# Supplies.net
KiCad netlist of a schematic drawn in Altium Designer
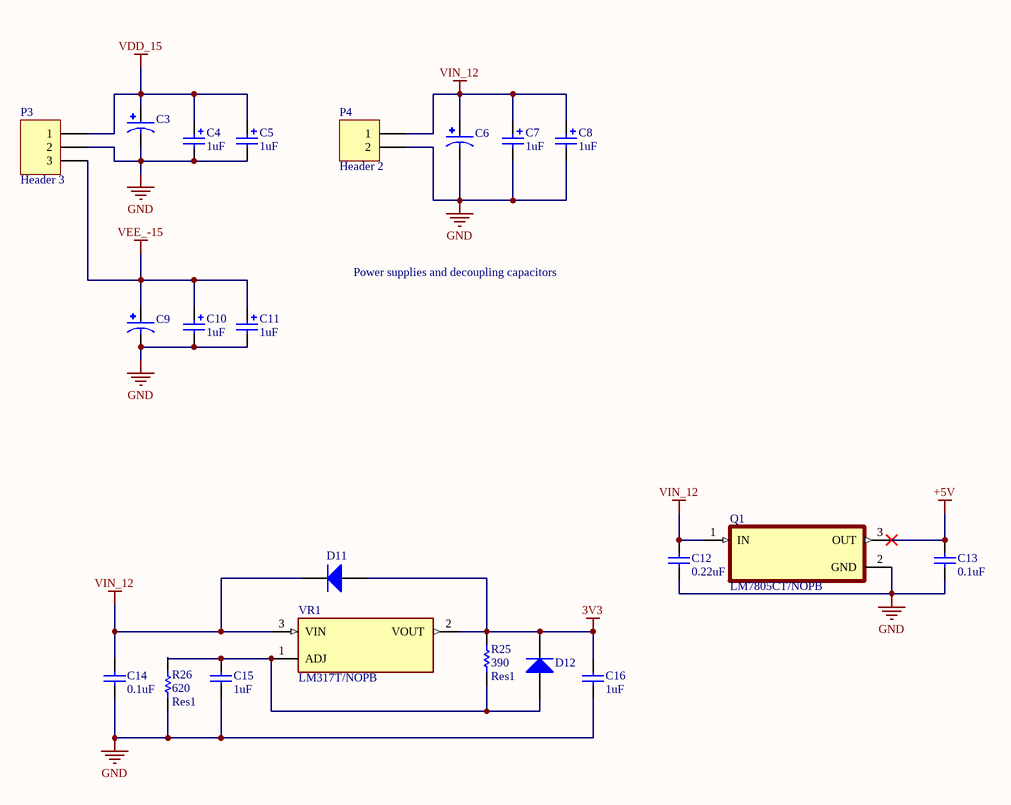
[diagram p0: Supplies.SchDoc]

(export (version "E")
  (design (tool "Eeschema 10.0.6"))
  (components
    (comp (ref "C3")
      (value "ECA2AM100B")
      (footprint "CAPPRD500W50D500H1100")
      (description "10ÂµF 100V Aluminum Electrolytic Capacitors Radial, Can 2000 Hrs @ 85Â°C")
      (fields (field (name "MF") "Panasonic") (field (name "DIGI-KEY_PART_NUMBER") "P19556TB-ND"))
      (libsource (lib "10uF_capa_rad2ECA2AM100B") (part "ECA2AM100B"))
    )
    (comp (ref "C4")
      (value "1uF")
      (footprint "RAD-0.1")
      (description "Polarized Capacitor (Radial)")
      (fields (field (name "Comment") "Cap No Pol") (field (name "PUBLISHER") "Altium Limited"))
      (libsource (lib "LABSTEPS_Project") (part "Cap No Pol"))
    )
    (comp (ref "C5")
      (value "1uF")
      (footprint "RAD-0.1")
      (description "Polarized Capacitor (Radial)")
      (fields (field (name "Comment") "Cap No Pol") (field (name "PUBLISHER") "Altium Limited"))
      (libsource (lib "LABSTEPS_Project") (part "Cap No Pol"))
    )
    (comp (ref "C6")
      (value "ECA2AM100B")
      (footprint "CAPPRD500W50D500H1100")
      (description "10ÂµF 100V Aluminum Electrolytic Capacitors Radial, Can 2000 Hrs @ 85Â°C")
      (fields (field (name "MF") "Panasonic") (field (name "DIGI-KEY_PART_NUMBER") "P19556TB-ND"))
      (libsource (lib "10uF_capa_rad2ECA2AM100B") (part "ECA2AM100B"))
    )
    (comp (ref "C7")
      (value "1uF")
      (footprint "RAD-0.1")
      (description "Polarized Capacitor (Radial)")
      (fields (field (name "Comment") "Cap No Pol") (field (name "PUBLISHER") "Altium Limited"))
      (libsource (lib "LABSTEPS_Project") (part "Cap No Pol"))
    )
    (comp (ref "C8")
      (value "1uF")
      (footprint "RAD-0.1")
      (description "Polarized Capacitor (Radial)")
      (fields (field (name "Comment") "Cap No Pol") (field (name "PUBLISHER") "Altium Limited"))
      (libsource (lib "LABSTEPS_Project") (part "Cap No Pol"))
    )
    (comp (ref "C9")
      (value "ECA2AM100B")
      (footprint "CAPPRD500W50D500H1100")
      (description "10ÂµF 100V Aluminum Electrolytic Capacitors Radial, Can 2000 Hrs @ 85Â°C")
      (fields (field (name "MF") "Panasonic") (field (name "DIGI-KEY_PART_NUMBER") "P19556TB-ND"))
      (libsource (lib "10uF_capa_rad2ECA2AM100B") (part "ECA2AM100B"))
    )
    (comp (ref "C10")
      (value "1uF")
      (footprint "RAD-0.1")
      (description "Polarized Capacitor (Radial)")
      (fields (field (name "Comment") "Cap No Pol") (field (name "PUBLISHER") "Altium Limited"))
      (libsource (lib "LABSTEPS_Project") (part "Cap No Pol"))
    )
    (comp (ref "C11")
      (value "1uF")
      (footprint "RAD-0.1")
      (description "Polarized Capacitor (Radial)")
      (fields (field (name "Comment") "Cap No Pol") (field (name "PUBLISHER") "Altium Limited"))
      (libsource (lib "LABSTEPS_Project") (part "Cap No Pol"))
    )
    (comp (ref "C12")
      (value "0.22uF")
      (footprint "RAD-0.3")
      (description "Capacitor")
      (fields (field (name "Comment") "Cap") (field (name "PUBLISHER") "Altium Limited"))
      (libsource (lib "Miscellaneous Devices") (part "Cap"))
    )
    (comp (ref "C13")
      (value "0.1uF")
      (footprint "RAD-0.3")
      (description "Capacitor")
      (fields (field (name "Comment") "Cap") (field (name "PUBLISHER") "Altium Limited"))
      (libsource (lib "Miscellaneous Devices") (part "Cap"))
    )
    (comp (ref "C14")
      (value "0.1uF")
      (footprint "RAD-0.3")
      (description "Capacitor")
      (fields (field (name "Comment") "Cap") (field (name "PUBLISHER") "Altium Limited"))
      (libsource (lib "Miscellaneous Devices") (part "Cap"))
    )
    (comp (ref "C15")
      (value "1uF")
      (footprint "RAD-0.3")
      (description "Capacitor")
      (fields (field (name "Comment") "Cap") (field (name "PUBLISHER") "Altium Limited"))
      (libsource (lib "Miscellaneous Devices") (part "Cap"))
    )
    (comp (ref "C16")
      (value "1uF")
      (footprint "RAD-0.3")
      (description "Capacitor")
      (fields (field (name "Comment") "Cap") (field (name "PUBLISHER") "Altium Limited"))
      (libsource (lib "Miscellaneous Devices") (part "Cap"))
    )
    (comp (ref "D11")
      (value "Diode 1N4001")
      (footprint "DO-41")
      (description "1 Amp General Purpose Rectifier")
      (fields (field (name "PUBLISHER") "Altium Limited"))
      (libsource (lib "Miscellaneous Devices") (part "Diode 1N4001"))
    )
    (comp (ref "D12")
      (value "Diode 1N4001")
      (footprint "DO-41")
      (description "1 Amp General Purpose Rectifier")
      (fields (field (name "PUBLISHER") "Altium Limited"))
      (libsource (lib "Miscellaneous Devices") (part "Diode 1N4001"))
    )
    (comp (ref "P3")
      (value "Header 3")
      (footprint "HDR1X3")
      (description "Header, 3-Pin")
      (fields (field (name "PUBLISHER") "Altium Limited"))
      (libsource (lib "Miscellaneous Connectors") (part "Header 3"))
    )
    (comp (ref "P4")
      (value "Header 2")
      (footprint "HDR1X2")
      (description "Header, 2-Pin")
      (fields (field (name "PUBLISHER") "Altium Limited"))
      (libsource (lib "Miscellaneous Connectors") (part "Header 2"))
    )
    (comp (ref "Q1")
      (value "LM7805CT/NOPB")
      (footprint "TO254P1054X470X1955-3")
      (libsource (lib "LM7805CT_NOPB") (part "LM7805CT/NOPB"))
    )
    (comp (ref "R25")
      (value "Res1")
      (footprint "AXIAL-0.4")
      (description "Resistor")
      (fields (field (name "ALTIUM_VALUE") "390") (field (name "PUBLISHER") "Altium Limited"))
      (libsource (lib "Miscellaneous Devices") (part "Res1"))
    )
    (comp (ref "R26")
      (value "Res1")
      (footprint "AXIAL-0.4")
      (description "Resistor")
      (fields (field (name "ALTIUM_VALUE") "620") (field (name "PUBLISHER") "Altium Limited"))
      (libsource (lib "Miscellaneous Devices") (part "Res1"))
    )
    (comp (ref "VR1")
      (value "LM317T/NOPB")
      (footprint "TO254P1054X470X1955-3")
      (description "1.5-A, 40-V, adjustable linear voltage regulator")
      (fields (field (name "MF") "Texas Instruments"))
      (libsource (lib "LM317T_NOPB") (part "LM317T/NOPB"))
    )
  )
  (nets
    (net (code "1") (name "+5V") (class "Default")
      (node (ref "C13") (pin "1") (pinfunction "1_1") (pintype "passive"))
      (node (ref "Q1") (pin "3") (pinfunction "OUT_3") (pintype "output"))
    )
    (net (code "2") (name "3V3") (class "Default")
      (node (ref "C16") (pin "1") (pinfunction "1_1") (pintype "passive"))
      (node (ref "D11") (pin "1") (pinfunction "A_1") (pintype "passive"))
      (node (ref "D12") (pin "2") (pinfunction "K_2") (pintype "passive"))
      (node (ref "R25") (pin "2") (pinfunction "2_2") (pintype "passive"))
      (node (ref "VR1") (pin "2") (pinfunction "VOUT_2") (pintype "output"))
    )
    (net (code "3") (name "GND") (class "Default")
      (node (ref "C10") (pin "2") (pinfunction "2_2") (pintype "passive"))
      (node (ref "C11") (pin "2") (pinfunction "2_2") (pintype "passive"))
      (node (ref "C12") (pin "2") (pinfunction "2_2") (pintype "passive"))
      (node (ref "C13") (pin "2") (pinfunction "2_2") (pintype "passive"))
      (node (ref "C14") (pin "2") (pinfunction "2_2") (pintype "passive"))
      (node (ref "C15") (pin "2") (pinfunction "2_2") (pintype "passive"))
      (node (ref "C16") (pin "2") (pinfunction "2_2") (pintype "passive"))
      (node (ref "C3") (pin "N") (pinfunction "N_N") (pintype "passive"))
      (node (ref "C4") (pin "2") (pinfunction "2_2") (pintype "passive"))
      (node (ref "C5") (pin "2") (pinfunction "2_2") (pintype "passive"))
      (node (ref "C6") (pin "N") (pinfunction "N_N") (pintype "passive"))
      (node (ref "C7") (pin "2") (pinfunction "2_2") (pintype "passive"))
      (node (ref "C8") (pin "2") (pinfunction "2_2") (pintype "passive"))
      (node (ref "C9") (pin "N") (pinfunction "N_N") (pintype "passive"))
      (node (ref "P3") (pin "2") (pinfunction "2_2") (pintype "passive"))
      (node (ref "P4") (pin "2") (pinfunction "2_2") (pintype "passive"))
      (node (ref "Q1") (pin "2") (pinfunction "GND_2") (pintype "power_in"))
      (node (ref "R26") (pin "1") (pinfunction "1_1") (pintype "passive"))
    )
    (net (code "4") (name "Net-(D12-A)") (class "Default")
      (node (ref "C15") (pin "1") (pinfunction "1_1") (pintype "passive"))
      (node (ref "D12") (pin "1") (pinfunction "A_1") (pintype "passive"))
      (node (ref "R25") (pin "1") (pinfunction "1_1") (pintype "passive"))
      (node (ref "R26") (pin "2") (pinfunction "2_2") (pintype "passive"))
      (node (ref "VR1") (pin "1") (pinfunction "ADJ_1") (pintype "passive"))
    )
    (net (code "5") (name "VDD_15") (class "Default")
      (node (ref "C3") (pin "P") (pinfunction "P_P") (pintype "passive"))
      (node (ref "C4") (pin "1") (pinfunction "1_1") (pintype "passive"))
      (node (ref "C5") (pin "1") (pinfunction "1_1") (pintype "passive"))
      (node (ref "P3") (pin "1") (pinfunction "1_1") (pintype "passive"))
    )
    (net (code "6") (name "VEE_-15") (class "Default")
      (node (ref "C10") (pin "1") (pinfunction "1_1") (pintype "passive"))
      (node (ref "C11") (pin "1") (pinfunction "1_1") (pintype "passive"))
      (node (ref "C9") (pin "P") (pinfunction "P_P") (pintype "passive"))
      (node (ref "P3") (pin "3") (pinfunction "3_3") (pintype "passive"))
    )
    (net (code "7") (name "VIN_12") (class "Default")
      (node (ref "C12") (pin "1") (pinfunction "1_1") (pintype "passive"))
      (node (ref "C14") (pin "1") (pinfunction "1_1") (pintype "passive"))
      (node (ref "C6") (pin "P") (pinfunction "P_P") (pintype "passive"))
      (node (ref "C7") (pin "1") (pinfunction "1_1") (pintype "passive"))
      (node (ref "C8") (pin "1") (pinfunction "1_1") (pintype "passive"))
      (node (ref "D11") (pin "2") (pinfunction "K_2") (pintype "passive"))
      (node (ref "P4") (pin "1") (pinfunction "1_1") (pintype "passive"))
      (node (ref "Q1") (pin "1") (pinfunction "IN_1") (pintype "input"))
      (node (ref "VR1") (pin "3") (pinfunction "VIN_3") (pintype "input"))
    )
  )
)
